# 74xx04-step-gen.net
KiCad netlist of a schematic drawn in EAGLE
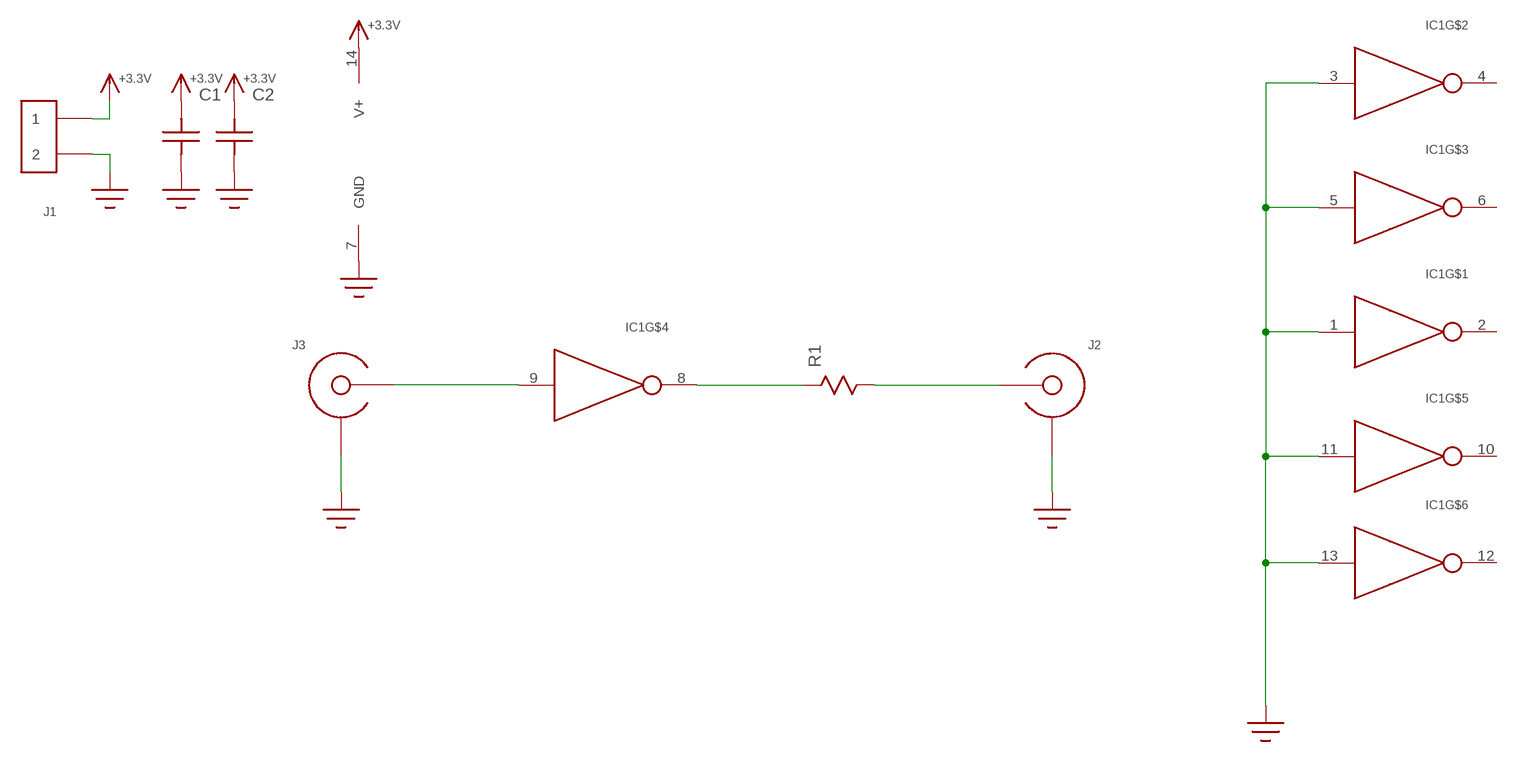
[diagram p0: schematic, sheet 1]

(export (version "E")
  (design (tool "Eeschema 10.0.6"))
  (components
    (comp (ref "C1")
      (value "C1206")
      (footprint "eagle-import:1206")
      (libsource (lib "eagle-import") (part "C1206"))
    )
    (comp (ref "C2")
      (value "C0603")
      (footprint "eagle-import:C0603")
      (libsource (lib "eagle-import") (part "C0603"))
    )
    (comp (ref "IC1")
      (value "74XX04")
      (footprint "eagle-import:SOIC-14")
      (libsource (lib "eagle-import") (part "74XX04"))
    )
    (comp (ref "J1")
      (value "HEADER_2PIN")
      (footprint "eagle-import:HEADER_2PIN")
      (libsource (lib "eagle-import") (part "HEADER_2PIN"))
    )
    (comp (ref "J2")
      (value "SMA-EDGE-LAUNCH4020_TAPER")
      (footprint "eagle-import:SMA_EDGE_LAUNCH_2L_4020_TAPER")
      (libsource (lib "eagle-import") (part "SMA-EDGE-LAUNCH4020_TAPER"))
    )
    (comp (ref "J3")
      (value "SMA-EDGE-LAUNCH4020_TAPER")
      (footprint "eagle-import:SMA_EDGE_LAUNCH_2L_4020_TAPER")
      (libsource (lib "eagle-import") (part "SMA-EDGE-LAUNCH4020_TAPER"))
    )
    (comp (ref "R1")
      (value "R0603")
      (footprint "eagle-import:R0603")
      (libsource (lib "eagle-import") (part "R0603"))
    )
  )
  (nets
    (net (code "1") (name "+3.3V") (class "Default")
      (node (ref "C1") (pin "P$2") (pinfunction "P$2_P$2") (pintype "bidirectional"))
      (node (ref "C2") (pin "P$2") (pinfunction "P$2_P$2") (pintype "bidirectional"))
      (node (ref "IC1") (pin "14") (pinfunction "V+_14") (pintype "bidirectional"))
      (node (ref "J1") (pin "1") (pinfunction "1_1") (pintype "bidirectional"))
    )
    (net (code "2") (name "GND") (class "Default")
      (node (ref "C1") (pin "P$1") (pinfunction "P$1_P$1") (pintype "bidirectional"))
      (node (ref "C2") (pin "P$1") (pinfunction "P$1_P$1") (pintype "bidirectional"))
      (node (ref "IC1") (pin "1") (pinfunction "IN_1") (pintype "bidirectional"))
      (node (ref "IC1") (pin "11") (pinfunction "IN_11") (pintype "bidirectional"))
      (node (ref "IC1") (pin "13") (pinfunction "IN_13") (pintype "bidirectional"))
      (node (ref "IC1") (pin "3") (pinfunction "IN_3") (pintype "bidirectional"))
      (node (ref "IC1") (pin "5") (pinfunction "IN_5") (pintype "bidirectional"))
      (node (ref "IC1") (pin "7") (pinfunction "GND_7") (pintype "bidirectional"))
      (node (ref "J1") (pin "2") (pinfunction "2_2") (pintype "bidirectional"))
      (node (ref "J2") (pin "BOTTOM_GND") (pinfunction "SHIELD_BOTTOM_GND") (pintype "bidirectional"))
      (node (ref "J2") (pin "GND@1") (pinfunction "SHIELD_GND@1") (pintype "bidirectional"))
      (node (ref "J2") (pin "GND@14") (pinfunction "SHIELD_GND@14") (pintype "bidirectional"))
      (node (ref "J2") (pin "GND@15") (pinfunction "SHIELD_GND@15") (pintype "bidirectional"))
      (node (ref "J2") (pin "GND@16") (pinfunction "SHIELD_GND@16") (pintype "bidirectional"))
      (node (ref "J2") (pin "GND@17") (pinfunction "SHIELD_GND@17") (pintype "bidirectional"))
      (node (ref "J2") (pin "GND@2") (pinfunction "SHIELD_GND@2") (pintype "bidirectional"))
      (node (ref "J2") (pin "GND@3") (pinfunction "SHIELD_GND@3") (pintype "bidirectional"))
      (node (ref "J2") (pin "GND@4") (pinfunction "SHIELD_GND@4") (pintype "bidirectional"))
      (node (ref "J2") (pin "GND@5") (pinfunction "SHIELD_GND@5") (pintype "bidirectional"))
      (node (ref "J2") (pin "GND@6") (pinfunction "SHIELD_GND@6") (pintype "bidirectional"))
      (node (ref "J2") (pin "GND@7") (pinfunction "SHIELD_GND@7") (pintype "bidirectional"))
      (node (ref "J2") (pin "GND@8") (pinfunction "SHIELD_GND@8") (pintype "bidirectional"))
      (node (ref "J2") (pin "GND_PAD1") (pinfunction "SHIELD_GND_PAD1") (pintype "bidirectional"))
      (node (ref "J2") (pin "GND_PAD2") (pinfunction "SHIELD_GND_PAD2") (pintype "bidirectional"))
      (node (ref "J2") (pin "P$1") (pinfunction "SHIELD_P$1") (pintype "bidirectional"))
      (node (ref "J2") (pin "P$2") (pinfunction "SHIELD_P$2") (pintype "bidirectional"))
      (node (ref "J3") (pin "BOTTOM_GND") (pinfunction "SHIELD_BOTTOM_GND") (pintype "bidirectional"))
      (node (ref "J3") (pin "GND@1") (pinfunction "SHIELD_GND@1") (pintype "bidirectional"))
      (node (ref "J3") (pin "GND@14") (pinfunction "SHIELD_GND@14") (pintype "bidirectional"))
      (node (ref "J3") (pin "GND@15") (pinfunction "SHIELD_GND@15") (pintype "bidirectional"))
      (node (ref "J3") (pin "GND@16") (pinfunction "SHIELD_GND@16") (pintype "bidirectional"))
      (node (ref "J3") (pin "GND@17") (pinfunction "SHIELD_GND@17") (pintype "bidirectional"))
      (node (ref "J3") (pin "GND@2") (pinfunction "SHIELD_GND@2") (pintype "bidirectional"))
      (node (ref "J3") (pin "GND@3") (pinfunction "SHIELD_GND@3") (pintype "bidirectional"))
      (node (ref "J3") (pin "GND@4") (pinfunction "SHIELD_GND@4") (pintype "bidirectional"))
      (node (ref "J3") (pin "GND@5") (pinfunction "SHIELD_GND@5") (pintype "bidirectional"))
      (node (ref "J3") (pin "GND@6") (pinfunction "SHIELD_GND@6") (pintype "bidirectional"))
      (node (ref "J3") (pin "GND@7") (pinfunction "SHIELD_GND@7") (pintype "bidirectional"))
      (node (ref "J3") (pin "GND@8") (pinfunction "SHIELD_GND@8") (pintype "bidirectional"))
      (node (ref "J3") (pin "GND_PAD1") (pinfunction "SHIELD_GND_PAD1") (pintype "bidirectional"))
      (node (ref "J3") (pin "GND_PAD2") (pinfunction "SHIELD_GND_PAD2") (pintype "bidirectional"))
      (node (ref "J3") (pin "P$1") (pinfunction "SHIELD_P$1") (pintype "bidirectional"))
      (node (ref "J3") (pin "P$2") (pinfunction "SHIELD_P$2") (pintype "bidirectional"))
    )
    (net (code "3") (name "Net-(IC1D-IN)") (class "Default")
      (node (ref "IC1") (pin "9") (pinfunction "IN_9") (pintype "bidirectional"))
      (node (ref "J3") (pin "CENTER@1") (pinfunction "CENTER_CENTER@1") (pintype "bidirectional"))
    )
    (net (code "4") (name "Net-(IC1D-OUT)") (class "Default")
      (node (ref "IC1") (pin "8") (pinfunction "OUT_8") (pintype "bidirectional"))
      (node (ref "R1") (pin "P$1") (pinfunction "P$3_P$1") (pintype "bidirectional"))
    )
    (net (code "5") (name "Net-(J2-CENTER)") (class "Default")
      (node (ref "J2") (pin "CENTER@1") (pinfunction "CENTER_CENTER@1") (pintype "bidirectional"))
      (node (ref "R1") (pin "P$2") (pinfunction "P$4_P$2") (pintype "bidirectional"))
    )
    (net (code "6") (name "unconnected-(IC1A-OUT-Pad2)") (class "Default")
      (node (ref "IC1") (pin "2") (pinfunction "OUT_2") (pintype "bidirectional"))
    )
    (net (code "7") (name "unconnected-(IC1B-OUT-Pad4)") (class "Default")
      (node (ref "IC1") (pin "4") (pinfunction "OUT_4") (pintype "bidirectional"))
    )
    (net (code "8") (name "unconnected-(IC1C-OUT-Pad6)") (class "Default")
      (node (ref "IC1") (pin "6") (pinfunction "OUT_6") (pintype "bidirectional"))
    )
    (net (code "9") (name "unconnected-(IC1E-OUT-Pad10)") (class "Default")
      (node (ref "IC1") (pin "10") (pinfunction "OUT_10") (pintype "bidirectional"))
    )
    (net (code "10") (name "unconnected-(IC1F-OUT-Pad12)") (class "Default")
      (node (ref "IC1") (pin "12") (pinfunction "OUT_12") (pintype "bidirectional"))
    )
  )
)
